# StandUp.net
KiCad netlist of a schematic drawn in Altium Designer
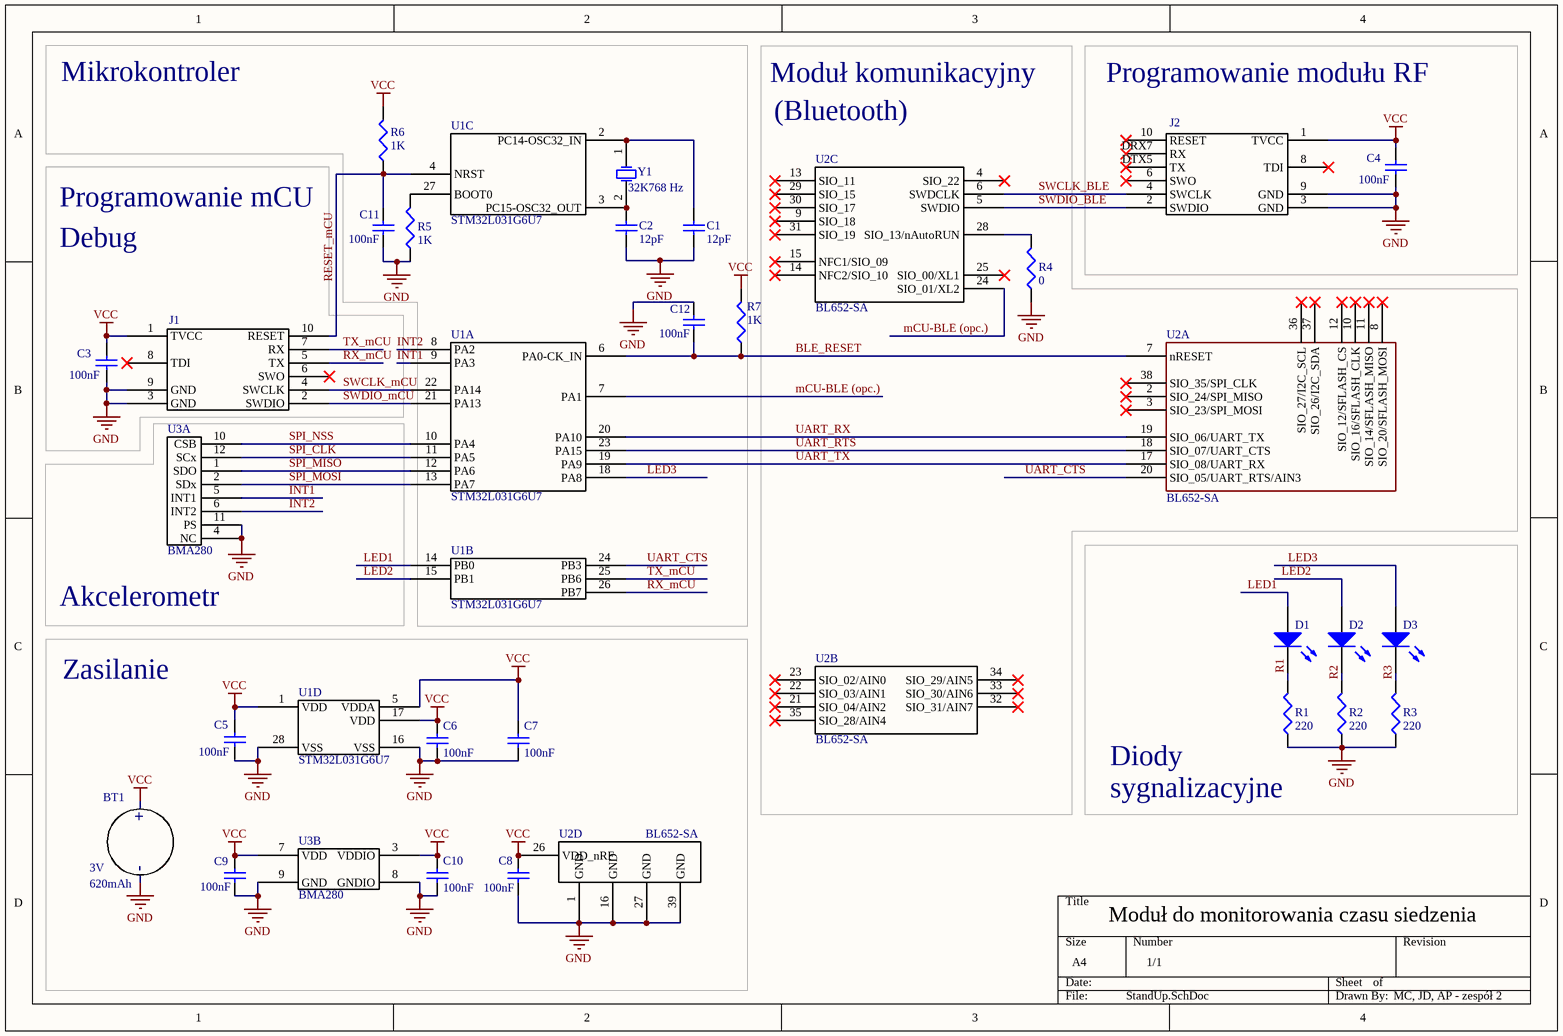
[diagram p0: StandUp.SchDoc]

(export (version "E")
  (design (tool "Eeschema 10.0.6"))
  (components
    (comp (ref "BT1")
      (value "SMTU2450N_LF")
      (footprint "SMTU2450N_LF")
      (fields (field (name "VOLTAGE") "3V") (field (name "CAPACITY") "620mAh"))
      (libsource (lib "AP_battery_holder_SMTU2450N_LF") (part "SMTU2450N_LF"))
    )
    (comp (ref "C1")
      (value "12pF")
      (footprint "0402")
      (description "Capacitor (Semiconductor SIM Model)")
      (fields (field (name "Comment") "Cap Semi") (field (name "PUBLISHER") "Altium Limited"))
      (libsource (lib "Miscellaneous Devices") (part "Cap Semi"))
    )
    (comp (ref "C2")
      (value "12pF")
      (footprint "0402")
      (description "Capacitor (Semiconductor SIM Model)")
      (fields (field (name "Comment") "Cap Semi") (field (name "PUBLISHER") "Altium Limited"))
      (libsource (lib "Miscellaneous Devices") (part "Cap Semi"))
    )
    (comp (ref "C3")
      (value "100nF")
      (footprint "0402")
      (description "Capacitor (Semiconductor SIM Model)")
      (fields (field (name "Comment") "Cap Semi") (field (name "PUBLISHER") "Altium Limited"))
      (libsource (lib "Miscellaneous Devices") (part "Cap Semi"))
    )
    (comp (ref "C4")
      (value "100nF")
      (footprint "0402")
      (description "Capacitor (Semiconductor SIM Model)")
      (fields (field (name "Comment") "Cap Semi") (field (name "PUBLISHER") "Altium Limited"))
      (libsource (lib "Miscellaneous Devices") (part "Cap Semi"))
    )
    (comp (ref "C5")
      (value "100nF")
      (footprint "0402")
      (description "Capacitor (Semiconductor SIM Model)")
      (fields (field (name "PUBLISHER") "Altium Limited"))
      (libsource (lib "Miscellaneous Devices") (part "Cap Semi"))
    )
    (comp (ref "C6")
      (value "100nF")
      (footprint "0402")
      (description "Capacitor (Semiconductor SIM Model)")
      (fields (field (name "PUBLISHER") "Altium Limited"))
      (libsource (lib "Miscellaneous Devices") (part "Cap Semi"))
    )
    (comp (ref "C7")
      (value "100nF")
      (footprint "0402")
      (description "Capacitor (Semiconductor SIM Model)")
      (fields (field (name "PUBLISHER") "Altium Limited"))
      (libsource (lib "Miscellaneous Devices") (part "Cap Semi"))
    )
    (comp (ref "C8")
      (value "100nF")
      (footprint "0402")
      (description "Capacitor (Semiconductor SIM Model)")
      (fields (field (name "PUBLISHER") "Altium Limited"))
      (libsource (lib "Miscellaneous Devices") (part "Cap Semi"))
    )
    (comp (ref "C9")
      (value "100nF")
      (footprint "0402")
      (description "Capacitor (Semiconductor SIM Model)")
      (fields (field (name "PUBLISHER") "Altium Limited"))
      (libsource (lib "Miscellaneous Devices") (part "Cap Semi"))
    )
    (comp (ref "C10")
      (value "100nF")
      (footprint "0402")
      (description "Capacitor (Semiconductor SIM Model)")
      (fields (field (name "PUBLISHER") "Altium Limited"))
      (libsource (lib "Miscellaneous Devices") (part "Cap Semi"))
    )
    (comp (ref "C11")
      (value "100nF")
      (footprint "0402")
      (description "Capacitor (Semiconductor SIM Model)")
      (fields (field (name "Comment") "Cap Semi") (field (name "PUBLISHER") "Altium Limited"))
      (libsource (lib "Miscellaneous Devices") (part "Cap Semi"))
    )
    (comp (ref "C12")
      (value "100nF")
      (footprint "0402")
      (description "Capacitor (Semiconductor SIM Model)")
      (fields (field (name "Comment") "Cap Semi") (field (name "PUBLISHER") "Altium Limited"))
      (libsource (lib "Miscellaneous Devices") (part "Cap Semi"))
    )
    (comp (ref "D1")
      (value "LED2")
      (footprint "MC_DIODE")
      (description "Typical RED, GREEN, YELLOW, AMBER GaAs LED")
      (fields (field (name "PUBLISHER") "Altium Limited"))
      (libsource (lib "Miscellaneous Devices") (part "LED2"))
    )
    (comp (ref "D2")
      (value "LED2")
      (footprint "MC_DIODE")
      (description "Typical RED, GREEN, YELLOW, AMBER GaAs LED")
      (fields (field (name "PUBLISHER") "Altium Limited"))
      (libsource (lib "Miscellaneous Devices") (part "LED2"))
    )
    (comp (ref "D3")
      (value "LED2")
      (footprint "MC_DIODE")
      (description "Typical RED, GREEN, YELLOW, AMBER GaAs LED")
      (fields (field (name "PUBLISHER") "Altium Limited"))
      (libsource (lib "Miscellaneous Devices") (part "LED2"))
    )
    (comp (ref "J1")
      (value "Cortez JTAG_UART")
      (footprint "MC_JTAG")
      (libsource (lib "MC_PBL4_Schlib") (part "MC_JTAG"))
    )
    (comp (ref "J2") (value "Cortez JTAG_UART") (footprint "MC_JTAG") (libsource (lib "") (part "MC_JTAG_1")))
    (comp (ref "R1")
      (value "220")
      (footprint "0402")
      (description "Resistor")
      (fields (field (name "Comment") "Res3") (field (name "PUBLISHER") "Altium Limited"))
      (libsource (lib "Miscellaneous Devices") (part "Res3"))
    )
    (comp (ref "R2")
      (value "220")
      (footprint "0402")
      (description "Resistor")
      (fields (field (name "Comment") "Res3") (field (name "PUBLISHER") "Altium Limited"))
      (libsource (lib "Miscellaneous Devices") (part "Res3"))
    )
    (comp (ref "R3")
      (value "220")
      (footprint "0402")
      (description "Resistor")
      (fields (field (name "Comment") "Res3") (field (name "PUBLISHER") "Altium Limited"))
      (libsource (lib "Miscellaneous Devices") (part "Res3"))
    )
    (comp (ref "R4")
      (value "0")
      (footprint "0402")
      (description "Resistor")
      (fields (field (name "Comment") "Res3") (field (name "PUBLISHER") "Altium Limited"))
      (libsource (lib "Miscellaneous Devices") (part "Res3"))
    )
    (comp (ref "R5")
      (value "1K")
      (footprint "0402")
      (description "Resistor")
      (fields (field (name "Comment") "Res3") (field (name "PUBLISHER") "Altium Limited"))
      (libsource (lib "Miscellaneous Devices") (part "Res3"))
    )
    (comp (ref "R6")
      (value "1K")
      (footprint "0402")
      (description "Resistor")
      (fields (field (name "Comment") "Res3") (field (name "PUBLISHER") "Altium Limited"))
      (libsource (lib "Miscellaneous Devices") (part "Res3"))
    )
    (comp (ref "R7")
      (value "1K")
      (footprint "0402")
      (description "Resistor")
      (fields (field (name "Comment") "Res3") (field (name "PUBLISHER") "Altium Limited"))
      (libsource (lib "Miscellaneous Devices") (part "Res3"))
    )
    (comp (ref "U1")
      (value "STM32L031G6U7")
      (footprint "MC_UFQFPN-28")
      (libsource (lib "") (part "MC_STM32L031G6U7_1"))
    )
    (comp (ref "U2") (value "BL652-SA") (footprint "BL652") (libsource (lib "AP_BL652-SA") (part "BL652")))
    (comp (ref "U3") (value "BMA280") (footprint "JD_LGA") (libsource (lib "") (part "JD_BMA280_1")))
    (comp (ref "Y1")
      (value "XTAL")
      (footprint "MC_XTAL")
      (description "Crystal Oscillator")
      (fields (field (name "FREQUENCY") "32K768 Hz") (field (name "PUBLISHER") "Altium Limited"))
      (libsource (lib "Miscellaneous Devices") (part "XTAL"))
    )
  )
  (nets
    (net (code "1") (name "/BLE_RESET") (class "Default")
      (node (ref "C12") (pin "1") (pinfunction "1_1") (pintype "passive"))
      (node (ref "R7") (pin "1") (pinfunction "1_1") (pintype "passive"))
      (node (ref "U1") (pin "6") (pinfunction "PA0-CK_IN_6") (pintype "passive"))
      (node (ref "U2") (pin "7") (pinfunction "nRESET_7") (pintype "passive"))
    )
    (net (code "2") (name "/INT1") (class "Default")
      (node (ref "U1") (pin "9") (pinfunction "PA3_9") (pintype "passive"))
      (node (ref "U3") (pin "5") (pinfunction "INT1_5") (pintype "passive"))
    )
    (net (code "3") (name "/INT2") (class "Default")
      (node (ref "U1") (pin "8") (pinfunction "PA2_8") (pintype "passive"))
      (node (ref "U3") (pin "6") (pinfunction "INT2_6") (pintype "passive"))
    )
    (net (code "4") (name "/LED1") (class "Default")
      (node (ref "D1") (pin "1") (pinfunction "A_1") (pintype "passive"))
      (node (ref "U1") (pin "14") (pinfunction "PB0_14") (pintype "passive"))
    )
    (net (code "5") (name "/LED2") (class "Default")
      (node (ref "D2") (pin "1") (pinfunction "A_1") (pintype "passive"))
      (node (ref "U1") (pin "15") (pinfunction "PB1_15") (pintype "passive"))
    )
    (net (code "6") (name "/LED3") (class "Default")
      (node (ref "D3") (pin "1") (pinfunction "A_1") (pintype "passive"))
      (node (ref "U1") (pin "18") (pinfunction "PA8_18") (pintype "passive"))
    )
    (net (code "7") (name "/R1") (class "Default")
      (node (ref "D1") (pin "2") (pinfunction "K_2") (pintype "passive"))
      (node (ref "R1") (pin "2") (pinfunction "2_2") (pintype "passive"))
    )
    (net (code "8") (name "/R2") (class "Default")
      (node (ref "D2") (pin "2") (pinfunction "K_2") (pintype "passive"))
      (node (ref "R2") (pin "2") (pinfunction "2_2") (pintype "passive"))
    )
    (net (code "9") (name "/R3") (class "Default")
      (node (ref "D3") (pin "2") (pinfunction "K_2") (pintype "passive"))
      (node (ref "R3") (pin "2") (pinfunction "2_2") (pintype "passive"))
    )
    (net (code "10") (name "/RESET_mCU") (class "Default")
      (node (ref "C11") (pin "2") (pinfunction "2_2") (pintype "passive"))
      (node (ref "J1") (pin "10") (pinfunction "RESET_10") (pintype "passive"))
      (node (ref "R6") (pin "1") (pinfunction "1_1") (pintype "passive"))
      (node (ref "U1") (pin "4") (pinfunction "NRST_4") (pintype "passive"))
    )
    (net (code "11") (name "/RX_mCU") (class "Default")
      (node (ref "J1") (pin "5") (pinfunction "TX_5") (pintype "passive"))
      (node (ref "U1") (pin "26") (pinfunction "PB7_26") (pintype "passive"))
    )
    (net (code "12") (name "/SPI_CLK") (class "Default")
      (node (ref "U1") (pin "11") (pinfunction "PA5_11") (pintype "passive"))
      (node (ref "U3") (pin "12") (pinfunction "SCx_12") (pintype "passive"))
    )
    (net (code "13") (name "/SPI_MISO") (class "Default")
      (node (ref "U1") (pin "12") (pinfunction "PA6_12") (pintype "passive"))
      (node (ref "U3") (pin "1") (pinfunction "SDO_1") (pintype "passive"))
    )
    (net (code "14") (name "/SPI_MOSI") (class "Default")
      (node (ref "U1") (pin "13") (pinfunction "PA7_13") (pintype "passive"))
      (node (ref "U3") (pin "2") (pinfunction "SDx_2") (pintype "passive"))
    )
    (net (code "15") (name "/SPI_NSS") (class "Default")
      (node (ref "U1") (pin "10") (pinfunction "PA4_10") (pintype "passive"))
      (node (ref "U3") (pin "10") (pinfunction "CSB_10") (pintype "passive"))
    )
    (net (code "16") (name "/SWCLK_BLE") (class "Default")
      (node (ref "J2") (pin "4") (pinfunction "SWCLK_4") (pintype "passive"))
      (node (ref "U2") (pin "6") (pinfunction "SWDCLK_6") (pintype "passive"))
    )
    (net (code "17") (name "/SWCLK_mCU") (class "Default")
      (node (ref "J1") (pin "4") (pinfunction "SWCLK_4") (pintype "passive"))
      (node (ref "U1") (pin "22") (pinfunction "PA14_22") (pintype "passive"))
    )
    (net (code "18") (name "/SWDIO_BLE") (class "Default")
      (node (ref "J2") (pin "2") (pinfunction "SWDIO_2") (pintype "passive"))
      (node (ref "U2") (pin "5") (pinfunction "SWDIO_5") (pintype "passive"))
    )
    (net (code "19") (name "/SWDIO_mCU") (class "Default")
      (node (ref "J1") (pin "2") (pinfunction "SWDIO_2") (pintype "passive"))
      (node (ref "U1") (pin "21") (pinfunction "PA13_21") (pintype "passive"))
    )
    (net (code "20") (name "/TX_mCU") (class "Default")
      (node (ref "J1") (pin "7") (pinfunction "RX_7") (pintype "passive"))
      (node (ref "U1") (pin "25") (pinfunction "PB6_25") (pintype "passive"))
    )
    (net (code "21") (name "/UART_CTS") (class "Default")
      (node (ref "U1") (pin "24") (pinfunction "PB3_24") (pintype "passive"))
      (node (ref "U2") (pin "20") (pinfunction "SIO_05/UART_RTS/AIN3_20") (pintype "passive"))
    )
    (net (code "22") (name "/UART_RTS") (class "Default")
      (node (ref "U1") (pin "23") (pinfunction "PA15_23") (pintype "passive"))
      (node (ref "U2") (pin "18") (pinfunction "SIO_07/UART_CTS_18") (pintype "passive"))
    )
    (net (code "23") (name "/UART_RX") (class "Default")
      (node (ref "U1") (pin "20") (pinfunction "PA10_20") (pintype "passive"))
      (node (ref "U2") (pin "19") (pinfunction "SIO_06/UART_TX_19") (pintype "passive"))
    )
    (net (code "24") (name "/UART_TX") (class "Default")
      (node (ref "U1") (pin "19") (pinfunction "PA9_19") (pintype "passive"))
      (node (ref "U2") (pin "17") (pinfunction "SIO_08/UART_RX_17") (pintype "passive"))
    )
    (net (code "25") (name "/mCU-BLE (opc.)") (class "Default")
      (node (ref "U1") (pin "7") (pinfunction "PA1_7") (pintype "passive"))
      (node (ref "U2") (pin "24") (pinfunction "SIO_01/XL2_24") (pintype "passive"))
    )
    (net (code "26") (name "GND") (class "Default")
      (node (ref "C1") (pin "1") (pinfunction "1_1") (pintype "passive"))
      (node (ref "C10") (pin "1") (pinfunction "1_1") (pintype "passive"))
      (node (ref "C11") (pin "1") (pinfunction "1_1") (pintype "passive"))
      (node (ref "C12") (pin "2") (pinfunction "2_2") (pintype "passive"))
      (node (ref "C2") (pin "1") (pinfunction "1_1") (pintype "passive"))
      (node (ref "C3") (pin "2") (pinfunction "2_2") (pintype "passive"))
      (node (ref "C4") (pin "2") (pinfunction "2_2") (pintype "passive"))
      (node (ref "C5") (pin "1") (pinfunction "1_1") (pintype "passive"))
      (node (ref "C6") (pin "1") (pinfunction "1_1") (pintype "passive"))
      (node (ref "C7") (pin "1") (pinfunction "1_1") (pintype "passive"))
      (node (ref "C8") (pin "1") (pinfunction "1_1") (pintype "passive"))
      (node (ref "C9") (pin "1") (pinfunction "1_1") (pintype "passive"))
      (node (ref "J1") (pin "3") (pinfunction "GND_3") (pintype "passive"))
      (node (ref "J1") (pin "9") (pinfunction "GND_9") (pintype "passive"))
      (node (ref "J2") (pin "3") (pinfunction "GND_3") (pintype "passive"))
      (node (ref "J2") (pin "9") (pinfunction "GND_9") (pintype "passive"))
      (node (ref "R1") (pin "1") (pinfunction "1_1") (pintype "passive"))
      (node (ref "R2") (pin "1") (pinfunction "1_1") (pintype "passive"))
      (node (ref "R3") (pin "1") (pinfunction "1_1") (pintype "passive"))
      (node (ref "R4") (pin "1") (pinfunction "1_1") (pintype "passive"))
      (node (ref "R5") (pin "1") (pinfunction "1_1") (pintype "passive"))
      (node (ref "U1") (pin "16") (pinfunction "VSS_16") (pintype "passive"))
      (node (ref "U1") (pin "28") (pinfunction "VSS_28") (pintype "passive"))
      (node (ref "U2") (pin "1") (pinfunction "GND_1") (pintype "passive"))
      (node (ref "U2") (pin "16") (pinfunction "GND_16") (pintype "passive"))
      (node (ref "U2") (pin "27") (pinfunction "GND_27") (pintype "passive"))
      (node (ref "U2") (pin "39") (pinfunction "GND_39") (pintype "passive"))
      (node (ref "U3") (pin "11") (pinfunction "PS_11") (pintype "passive"))
      (node (ref "U3") (pin "4") (pinfunction "NC_4") (pintype "passive"))
      (node (ref "U3") (pin "8") (pinfunction "GNDIO_8") (pintype "passive"))
      (node (ref "U3") (pin "9") (pinfunction "GND_9") (pintype "passive"))
    )
    (net (code "27") (name "Net-(U1C-BOOT0)") (class "Default")
      (node (ref "R5") (pin "2") (pinfunction "2_2") (pintype "passive"))
      (node (ref "U1") (pin "27") (pinfunction "BOOT0_27") (pintype "passive"))
    )
    (net (code "28") (name "Net-(U1C-PC14-OSC32_IN)") (class "Default")
      (node (ref "C1") (pin "2") (pinfunction "2_2") (pintype "passive"))
      (node (ref "U1") (pin "2") (pinfunction "PC14-OSC32_IN_2") (pintype "passive"))
      (node (ref "Y1") (pin "1") (pinfunction "OSC1_1") (pintype "passive"))
    )
    (net (code "29") (name "Net-(U1C-PC15-OSC32_OUT)") (class "Default")
      (node (ref "C2") (pin "2") (pinfunction "2_2") (pintype "passive"))
      (node (ref "U1") (pin "3") (pinfunction "PC15-OSC32_OUT_3") (pintype "passive"))
      (node (ref "Y1") (pin "2") (pinfunction "OSC2_2") (pintype "passive"))
    )
    (net (code "30") (name "Net-(U2C-SIO_13{slash}nAutoRUN)") (class "Default")
      (node (ref "R4") (pin "2") (pinfunction "2_2") (pintype "passive"))
      (node (ref "U2") (pin "28") (pinfunction "SIO_13/nAutoRUN_28") (pintype "passive"))
    )
    (net (code "31") (name "VCC") (class "Default")
      (node (ref "C10") (pin "2") (pinfunction "2_2") (pintype "passive"))
      (node (ref "C3") (pin "1") (pinfunction "1_1") (pintype "passive"))
      (node (ref "C4") (pin "1") (pinfunction "1_1") (pintype "passive"))
      (node (ref "C5") (pin "2") (pinfunction "2_2") (pintype "passive"))
      (node (ref "C6") (pin "2") (pinfunction "2_2") (pintype "passive"))
      (node (ref "C7") (pin "2") (pinfunction "2_2") (pintype "passive"))
      (node (ref "C8") (pin "2") (pinfunction "2_2") (pintype "passive"))
      (node (ref "C9") (pin "2") (pinfunction "2_2") (pintype "passive"))
      (node (ref "J1") (pin "1") (pinfunction "TVCC_1") (pintype "passive"))
      (node (ref "J2") (pin "1") (pinfunction "TVCC_1") (pintype "passive"))
      (node (ref "R6") (pin "2") (pinfunction "2_2") (pintype "passive"))
      (node (ref "R7") (pin "2") (pinfunction "2_2") (pintype "passive"))
      (node (ref "U1") (pin "1") (pinfunction "VDD_1") (pintype "passive"))
      (node (ref "U1") (pin "17") (pinfunction "VDD_17") (pintype "passive"))
      (node (ref "U1") (pin "5") (pinfunction "VDDA_5") (pintype "passive"))
      (node (ref "U2") (pin "26") (pinfunction "VDD_nRF_26") (pintype "passive"))
      (node (ref "U3") (pin "3") (pinfunction "VDDIO_3") (pintype "passive"))
      (node (ref "U3") (pin "7") (pinfunction "VDD_7") (pintype "passive"))
    )
    (net (code "32") (name "unconnected-(J1-SWO-Pad6)") (class "Default")
      (node (ref "J1") (pin "6") (pinfunction "SWO_6") (pintype "passive+no_connect"))
    )
    (net (code "33") (name "unconnected-(J1-TDI-Pad8)") (class "Default")
      (node (ref "J1") (pin "8") (pinfunction "TDI_8") (pintype "passive+no_connect"))
    )
    (net (code "34") (name "unconnected-(J2-RESET-Pad10)") (class "Default")
      (node (ref "J2") (pin "10") (pinfunction "RESET_10") (pintype "passive+no_connect"))
    )
    (net (code "35") (name "unconnected-(J2-RX-PadDRX7)") (class "Default")
      (node (ref "J2") (pin "DRX7") (pinfunction "RX_DRX7") (pintype "passive+no_connect"))
    )
    (net (code "36") (name "unconnected-(J2-SWO-Pad6)") (class "Default")
      (node (ref "J2") (pin "6") (pinfunction "SWO_6") (pintype "passive+no_connect"))
    )
    (net (code "37") (name "unconnected-(J2-TDI-Pad8)") (class "Default")
      (node (ref "J2") (pin "8") (pinfunction "TDI_8") (pintype "passive+no_connect"))
    )
    (net (code "38") (name "unconnected-(J2-TX-PadDTX5)") (class "Default")
      (node (ref "J2") (pin "DTX5") (pinfunction "TX_DTX5") (pintype "passive+no_connect"))
    )
    (net (code "39") (name "unconnected-(U2A-SIO_12{slash}SFLASH_CS-Pad12)") (class "Default")
      (node (ref "U2") (pin "12") (pinfunction "SIO_12/SFLASH_CS_12") (pintype "passive+no_connect"))
    )
    (net (code "40") (name "unconnected-(U2A-SIO_14{slash}SFLASH_MISO-Pad11)") (class "Default")
      (node (ref "U2") (pin "11") (pinfunction "SIO_14/SFLASH_MISO_11") (pintype "passive+no_connect"))
    )
    (net (code "41") (name "unconnected-(U2A-SIO_16{slash}SFLASH_CLK-Pad10)") (class "Default")
      (node (ref "U2") (pin "10") (pinfunction "SIO_16/SFLASH_CLK_10") (pintype "passive+no_connect"))
    )
    (net (code "42") (name "unconnected-(U2A-SIO_20{slash}SFLASH_MOSI-Pad8)") (class "Default")
      (node (ref "U2") (pin "8") (pinfunction "SIO_20/SFLASH_MOSI_8") (pintype "passive+no_connect"))
    )
    (net (code "43") (name "unconnected-(U2A-SIO_23{slash}SPI_MOSI-Pad3)") (class "Default")
      (node (ref "U2") (pin "3") (pinfunction "SIO_23/SPI_MOSI_3") (pintype "passive+no_connect"))
    )
    (net (code "44") (name "unconnected-(U2A-SIO_24{slash}SPI_MISO-Pad2)") (class "Default")
      (node (ref "U2") (pin "2") (pinfunction "SIO_24/SPI_MISO_2") (pintype "passive+no_connect"))
    )
    (net (code "45") (name "unconnected-(U2A-SIO_26{slash}I2C_SDA-Pad37)") (class "Default")
      (node (ref "U2") (pin "37") (pinfunction "SIO_26/I2C_SDA_37") (pintype "passive+no_connect"))
    )
    (net (code "46") (name "unconnected-(U2A-SIO_27{slash}I2C_SCL-Pad36)") (class "Default")
      (node (ref "U2") (pin "36") (pinfunction "SIO_27/I2C_SCL_36") (pintype "passive+no_connect"))
    )
    (net (code "47") (name "unconnected-(U2A-SIO_35{slash}SPI_CLK-Pad38)") (class "Default")
      (node (ref "U2") (pin "38") (pinfunction "SIO_35/SPI_CLK_38") (pintype "passive+no_connect"))
    )
    (net (code "48") (name "unconnected-(U2B-SIO_02{slash}AIN0-Pad23)") (class "Default")
      (node (ref "U2") (pin "23") (pinfunction "SIO_02/AIN0_23") (pintype "passive+no_connect"))
    )
    (net (code "49") (name "unconnected-(U2B-SIO_03{slash}AIN1-Pad22)") (class "Default")
      (node (ref "U2") (pin "22") (pinfunction "SIO_03/AIN1_22") (pintype "passive+no_connect"))
    )
    (net (code "50") (name "unconnected-(U2B-SIO_04{slash}AIN2-Pad21)") (class "Default")
      (node (ref "U2") (pin "21") (pinfunction "SIO_04/AIN2_21") (pintype "passive+no_connect"))
    )
    (net (code "51") (name "unconnected-(U2B-SIO_28{slash}AIN4-Pad35)") (class "Default")
      (node (ref "U2") (pin "35") (pinfunction "SIO_28/AIN4_35") (pintype "passive+no_connect"))
    )
    (net (code "52") (name "unconnected-(U2B-SIO_29{slash}AIN5-Pad34)") (class "Default")
      (node (ref "U2") (pin "34") (pinfunction "SIO_29/AIN5_34") (pintype "passive+no_connect"))
    )
    (net (code "53") (name "unconnected-(U2B-SIO_30{slash}AIN6-Pad33)") (class "Default")
      (node (ref "U2") (pin "33") (pinfunction "SIO_30/AIN6_33") (pintype "passive+no_connect"))
    )
    (net (code "54") (name "unconnected-(U2B-SIO_31{slash}AIN7-Pad32)") (class "Default")
      (node (ref "U2") (pin "32") (pinfunction "SIO_31/AIN7_32") (pintype "passive+no_connect"))
    )
    (net (code "55") (name "unconnected-(U2C-NFC1{slash}SIO_09-Pad15)") (class "Default")
      (node (ref "U2") (pin "15") (pinfunction "NFC1/SIO_09_15") (pintype "passive+no_connect"))
    )
    (net (code "56") (name "unconnected-(U2C-NFC2{slash}SIO_10-Pad14)") (class "Default")
      (node (ref "U2") (pin "14") (pinfunction "NFC2/SIO_10_14") (pintype "passive+no_connect"))
    )
    (net (code "57") (name "unconnected-(U2C-SIO_00{slash}XL1-Pad25)") (class "Default")
      (node (ref "U2") (pin "25") (pinfunction "SIO_00/XL1_25") (pintype "passive+no_connect"))
    )
    (net (code "58") (name "unconnected-(U2C-SIO_11-Pad13)") (class "Default")
      (node (ref "U2") (pin "13") (pinfunction "SIO_11_13") (pintype "passive+no_connect"))
    )
    (net (code "59") (name "unconnected-(U2C-SIO_15-Pad29)") (class "Default")
      (node (ref "U2") (pin "29") (pinfunction "SIO_15_29") (pintype "passive+no_connect"))
    )
    (net (code "60") (name "unconnected-(U2C-SIO_17-Pad30)") (class "Default")
      (node (ref "U2") (pin "30") (pinfunction "SIO_17_30") (pintype "passive+no_connect"))
    )
    (net (code "61") (name "unconnected-(U2C-SIO_18-Pad9)") (class "Default")
      (node (ref "U2") (pin "9") (pinfunction "SIO_18_9") (pintype "passive+no_connect"))
    )
    (net (code "62") (name "unconnected-(U2C-SIO_19-Pad31)") (class "Default")
      (node (ref "U2") (pin "31") (pinfunction "SIO_19_31") (pintype "passive+no_connect"))
    )
    (net (code "63") (name "unconnected-(U2C-SIO_22-Pad4)") (class "Default")
      (node (ref "U2") (pin "4") (pinfunction "SIO_22_4") (pintype "passive+no_connect"))
    )
  )
)
